# RLC.net
KiCad netlist of a schematic drawn in EAGLE
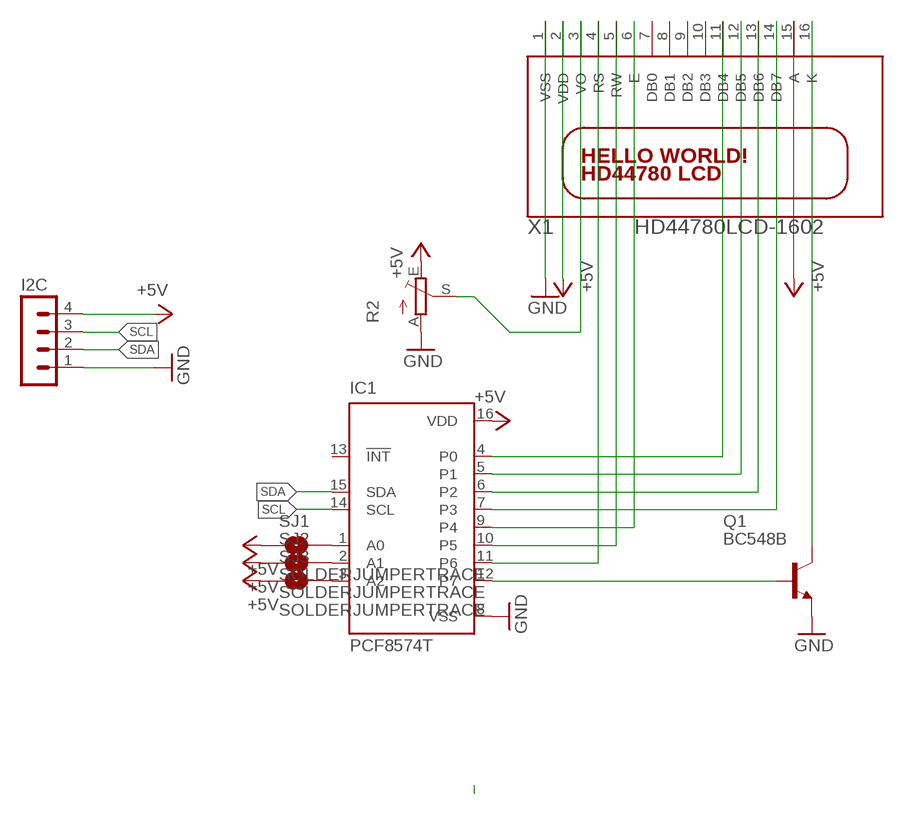
[diagram p0: schematic, sheet 1]

(export (version "E")
  (design (tool "Eeschema 10.0.6"))
  (components
    (comp (ref "I2C")
      (value "MA04-1")
      (footprint "eagle-import:MA04-1")
      (libsource (lib "eagle-import") (part "MA04-1"))
    )
    (comp (ref "IC1")
      (value "PCF8574T")
      (footprint "eagle-import:SO16W")
      (fields (field (name "MPN") "PCF8574T/3,512"))
      (libsource (lib "eagle-import") (part "PCF8574T"))
    )
    (comp (ref "Q1")
      (value "BC548B")
      (footprint "eagle-import:TO92-EBC")
      (libsource (lib "eagle-import") (part "BC548B"))
    )
    (comp (ref "R2")
      (value "TRIM_EU-CA6V")
      (footprint "eagle-import:CA6V")
      (libsource (lib "eagle-import") (part "TRIM_EU-CA6V"))
    )
    (comp (ref "SJ1")
      (value "SOLDERJUMPERTRACE")
      (footprint "eagle-import:SJ_2S-TRACE")
      (libsource (lib "eagle-import") (part "SOLDERJUMPERTRACE"))
    )
    (comp (ref "SJ2")
      (value "SOLDERJUMPERTRACE")
      (footprint "eagle-import:SJ_2S-TRACE")
      (libsource (lib "eagle-import") (part "SOLDERJUMPERTRACE"))
    )
    (comp (ref "SJ3")
      (value "SOLDERJUMPERTRACE")
      (footprint "eagle-import:SJ_2S-TRACE")
      (libsource (lib "eagle-import") (part "SOLDERJUMPERTRACE"))
    )
    (comp (ref "X1")
      (value "HD44780LCD-1602")
      (footprint "eagle-import:LCD1602")
      (libsource (lib "eagle-import") (part "HD44780LCD-1602"))
    )
  )
  (nets
    (net (code "1") (name "+5V") (class "Default")
      (node (ref "I2C") (pin "4") (pinfunction "4_4") (pintype "passive"))
      (node (ref "IC1") (pin "16") (pinfunction "VDD_16") (pintype "power_in"))
      (node (ref "R2") (pin "E") (pinfunction "E_E") (pintype "passive"))
      (node (ref "SJ1") (pin "1") (pinfunction "1_1") (pintype "passive"))
      (node (ref "SJ2") (pin "1") (pinfunction "1_1") (pintype "passive"))
      (node (ref "SJ3") (pin "1") (pinfunction "1_1") (pintype "passive"))
      (node (ref "X1") (pin "15") (pinfunction "A_15") (pintype "input"))
      (node (ref "X1") (pin "2") (pinfunction "VDD_2") (pintype "power_in"))
    )
    (net (code "2") (name "GND") (class "Default")
      (node (ref "I2C") (pin "1") (pinfunction "1_1") (pintype "passive"))
      (node (ref "IC1") (pin "8") (pinfunction "VSS_8") (pintype "power_in"))
      (node (ref "Q1") (pin "E") (pinfunction "E_E") (pintype "passive"))
      (node (ref "R2") (pin "A") (pinfunction "A_A") (pintype "passive"))
      (node (ref "X1") (pin "1") (pinfunction "VSS_1") (pintype "power_in"))
    )
    (net (code "3") (name "Net-(IC1-A0)") (class "Default")
      (node (ref "IC1") (pin "1") (pinfunction "A0_1") (pintype "input"))
      (node (ref "SJ1") (pin "2") (pinfunction "2_2") (pintype "passive"))
    )
    (net (code "4") (name "Net-(IC1-A1)") (class "Default")
      (node (ref "IC1") (pin "2") (pinfunction "A1_2") (pintype "input"))
      (node (ref "SJ2") (pin "2") (pinfunction "2_2") (pintype "passive"))
    )
    (net (code "5") (name "Net-(IC1-A2)") (class "Default")
      (node (ref "IC1") (pin "3") (pinfunction "A2_3") (pintype "input"))
      (node (ref "SJ3") (pin "2") (pinfunction "2_2") (pintype "passive"))
    )
    (net (code "6") (name "Net-(IC1-P0)") (class "Default")
      (node (ref "IC1") (pin "4") (pinfunction "P0_4") (pintype "bidirectional"))
      (node (ref "X1") (pin "11") (pinfunction "DB4_11") (pintype "bidirectional"))
    )
    (net (code "7") (name "Net-(IC1-P1)") (class "Default")
      (node (ref "IC1") (pin "5") (pinfunction "P1_5") (pintype "bidirectional"))
      (node (ref "X1") (pin "12") (pinfunction "DB5_12") (pintype "bidirectional"))
    )
    (net (code "8") (name "Net-(IC1-P2)") (class "Default")
      (node (ref "IC1") (pin "6") (pinfunction "P2_6") (pintype "bidirectional"))
      (node (ref "X1") (pin "13") (pinfunction "DB6_13") (pintype "bidirectional"))
    )
    (net (code "9") (name "Net-(IC1-P3)") (class "Default")
      (node (ref "IC1") (pin "7") (pinfunction "P3_7") (pintype "bidirectional"))
      (node (ref "X1") (pin "14") (pinfunction "DB7_14") (pintype "bidirectional"))
    )
    (net (code "10") (name "Net-(IC1-P4)") (class "Default")
      (node (ref "IC1") (pin "9") (pinfunction "P4_9") (pintype "bidirectional"))
      (node (ref "X1") (pin "6") (pinfunction "E_6") (pintype "input"))
    )
    (net (code "11") (name "Net-(IC1-P5)") (class "Default")
      (node (ref "IC1") (pin "10") (pinfunction "P5_10") (pintype "bidirectional"))
      (node (ref "X1") (pin "5") (pinfunction "RW_5") (pintype "input"))
    )
    (net (code "12") (name "Net-(IC1-P6)") (class "Default")
      (node (ref "IC1") (pin "11") (pinfunction "P6_11") (pintype "bidirectional"))
      (node (ref "X1") (pin "4") (pinfunction "RS_4") (pintype "input"))
    )
    (net (code "13") (name "Net-(IC1-P7)") (class "Default")
      (node (ref "IC1") (pin "12") (pinfunction "P7_12") (pintype "bidirectional"))
      (node (ref "Q1") (pin "B") (pinfunction "B_B") (pintype "passive"))
    )
    (net (code "14") (name "Net-(X1-K)") (class "Default")
      (node (ref "Q1") (pin "C") (pinfunction "C_C") (pintype "passive"))
      (node (ref "X1") (pin "16") (pinfunction "K_16") (pintype "input"))
    )
    (net (code "15") (name "Net-(X1-VO)") (class "Default")
      (node (ref "R2") (pin "S") (pinfunction "S_S") (pintype "passive"))
      (node (ref "X1") (pin "3") (pinfunction "VO_3") (pintype "input"))
    )
    (net (code "16") (name "SCL") (class "Default")
      (node (ref "I2C") (pin "3") (pinfunction "3_3") (pintype "passive"))
      (node (ref "IC1") (pin "14") (pinfunction "SCL_14") (pintype "input"))
    )
    (net (code "17") (name "SDA") (class "Default")
      (node (ref "I2C") (pin "2") (pinfunction "2_2") (pintype "passive"))
      (node (ref "IC1") (pin "15") (pinfunction "SDA_15") (pintype "bidirectional"))
    )
    (net (code "18") (name "unconnected-(IC1-~{INT}-Pad13)") (class "Default")
      (node (ref "IC1") (pin "13") (pinfunction "~{INT}_13") (pintype "output"))
    )
    (net (code "19") (name "unconnected-(X1-DB0-Pad7)") (class "Default")
      (node (ref "X1") (pin "7") (pinfunction "DB0_7") (pintype "bidirectional"))
    )
    (net (code "20") (name "unconnected-(X1-DB1-Pad8)") (class "Default")
      (node (ref "X1") (pin "8") (pinfunction "DB1_8") (pintype "bidirectional"))
    )
    (net (code "21") (name "unconnected-(X1-DB2-Pad9)") (class "Default")
      (node (ref "X1") (pin "9") (pinfunction "DB2_9") (pintype "bidirectional"))
    )
    (net (code "22") (name "unconnected-(X1-DB3-Pad10)") (class "Default")
      (node (ref "X1") (pin "10") (pinfunction "DB3_10") (pintype "bidirectional"))
    )
  )
)
